# 1_PWR.net
KiCad netlist of a schematic drawn in Altium Designer
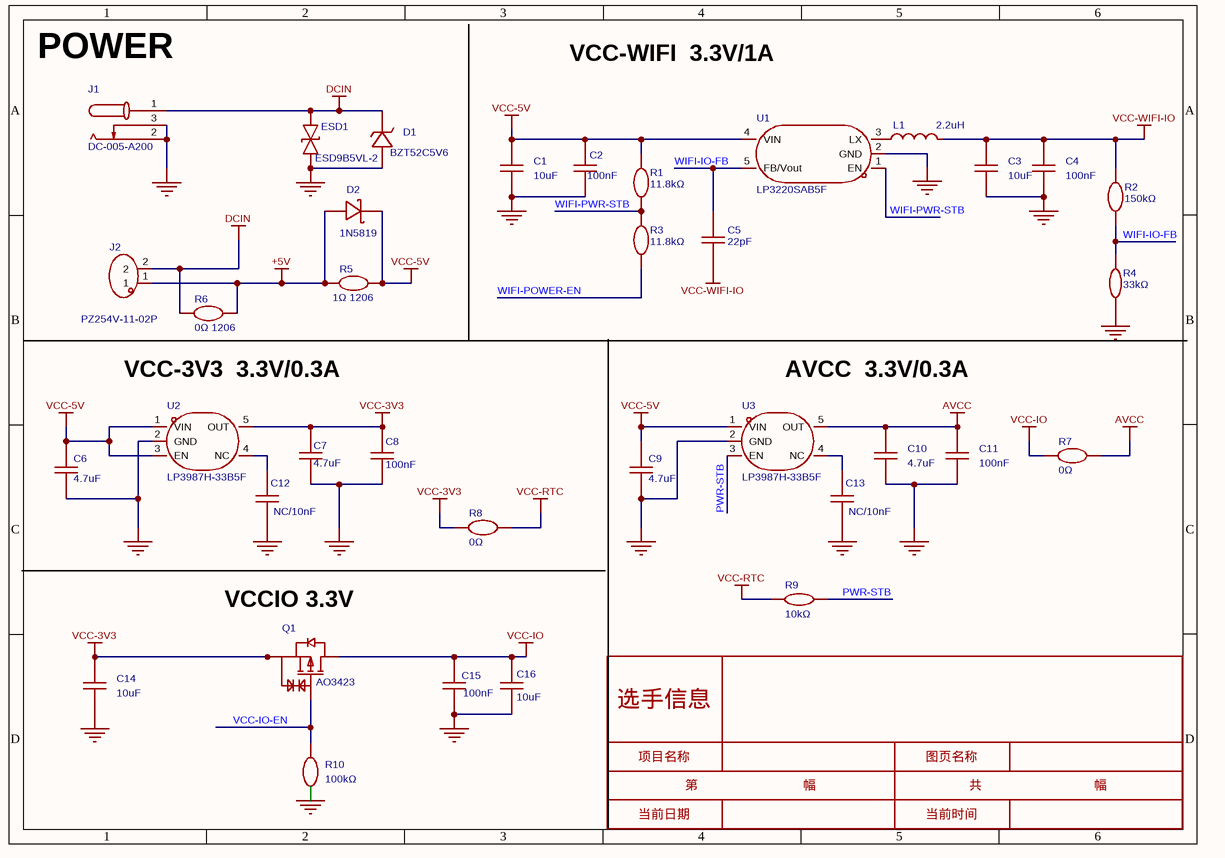
[diagram p0: 1_PWR.schdoc]

(export (version "E")
  (design (tool "Eeschema 10.0.6"))
  (components
    (comp (ref "C1")
      (value "10uF")
      (footprint "C0805")
      (description "容值:10uF;精度:±10%;额定电压:50V;温度系数:X5R;")
      (fields
        (field (name "MANUFACTURER") "HRE(芯声)")
        (field (name "MANUFACTURER PART") "CGA0805X5R106K500MT")
      )
      (libsource (lib "altium-import") (part "root_1_CGA0805X5R106K500MT_"))
    )
    (comp (ref "C2")
      (value "100nF")
      (footprint "C0402")
      (description "容值:100nF;精度:±10%;额定电压:16V;温度系数:X7R;")
      (fields
        (field (name "MANUFACTURER") "SAMSUNG(三星)")
        (field (name "MANUFACTURER PART") "CL05B104KO5NNNC")
      )
      (libsource (lib "altium-import") (part "root_1_CL05B104KO5NNNC_"))
    )
    (comp (ref "C3")
      (value "10uF")
      (footprint "C0805")
      (description "容值:10uF;精度:±10%;额定电压:50V;温度系数:X5R;")
      (fields
        (field (name "MANUFACTURER") "HRE(芯声)")
        (field (name "MANUFACTURER PART") "CGA0805X5R106K500MT")
      )
      (libsource (lib "altium-import") (part "root_1_CGA0805X5R106K500MT_"))
    )
    (comp (ref "C4")
      (value "100nF")
      (footprint "C0402")
      (description "容值:100nF;精度:±10%;额定电压:16V;温度系数:X7R;")
      (fields
        (field (name "MANUFACTURER") "SAMSUNG(三星)")
        (field (name "MANUFACTURER PART") "CL05B104KO5NNNC")
      )
      (libsource (lib "altium-import") (part "root_1_CL05B104KO5NNNC_"))
    )
    (comp (ref "C5")
      (value "22pF")
      (footprint "C0402")
      (description "容值:22pF;精度:±5%;额定电压:50V;温度系数:C0G;")
      (fields
        (field (name "MANUFACTURER") "FOJAN(富捷)")
        (field (name "MANUFACTURER PART") "FCC0402N220J500AT")
      )
      (libsource (lib "altium-import") (part "root_1_FCC0402N220J500AT_"))
    )
    (comp (ref "C6")
      (value "4.7uF")
      (footprint "C0402")
      (description "容值:4.7uF;精度:±20%;额定电压:25V;温度系数:-;")
      (fields
        (field (name "MANUFACTURER") "muRata(村田)")
        (field (name "MANUFACTURERPART") "GRM155C61E475ME15D")
      )
      (libsource (lib "altium-import") (part "root_1_GRM155C61E475ME15D_"))
    )
    (comp (ref "C7")
      (value "4.7uF")
      (footprint "C0402")
      (description "容值:4.7uF;精度:±20%;额定电压:25V;温度系数:-;")
      (fields
        (field (name "MANUFACTURER") "muRata(村田)")
        (field (name "MANUFACTURERPART") "GRM155C61E475ME15D")
      )
      (libsource (lib "altium-import") (part "root_1_GRM155C61E475ME15D_"))
    )
    (comp (ref "C8")
      (value "100nF")
      (footprint "C0402")
      (description "容值:100nF;精度:±10%;额定电压:16V;温度系数:X7R;")
      (fields (field (name "MANUFACTURER") "SAMSUNG(三星)") (field (name "MANUFACTURERPART") "CL05B104KO5NNNC"))
      (libsource (lib "altium-import") (part "root_1_CL05B104KO5NNNC_"))
    )
    (comp (ref "C9")
      (value "4.7uF")
      (footprint "C0402")
      (description "容值:4.7uF;精度:±20%;额定电压:25V;温度系数:-;")
      (fields
        (field (name "MANUFACTURER") "muRata(村田)")
        (field (name "MANUFACTURERPART") "GRM155C61E475ME15D")
      )
      (libsource (lib "altium-import") (part "root_1_GRM155C61E475ME15D_"))
    )
    (comp (ref "C10")
      (value "4.7uF")
      (footprint "C0402")
      (description "容值:4.7uF;精度:±20%;额定电压:25V;温度系数:-;")
      (fields
        (field (name "MANUFACTURER") "muRata(村田)")
        (field (name "MANUFACTURERPART") "GRM155C61E475ME15D")
      )
      (libsource (lib "altium-import") (part "root_1_GRM155C61E475ME15D_"))
    )
    (comp (ref "C11")
      (value "100nF")
      (footprint "C0402")
      (description "容值:100nF;精度:±10%;额定电压:16V;温度系数:X7R;")
      (fields (field (name "MANUFACTURER") "SAMSUNG(三星)") (field (name "MANUFACTURERPART") "CL05B104KO5NNNC"))
      (libsource (lib "altium-import") (part "root_1_CL05B104KO5NNNC_"))
    )
    (comp (ref "C12")
      (value "NC/10nF")
      (footprint "C0402")
      (description "容值:100nF;精度:±10%;额定电压:16V;温度系数:X7R;")
      (fields (field (name "MANUFACTURER") "SAMSUNG(三星)") (field (name "MANUFACTURERPART") "CL05B104KO5NNNC"))
      (libsource (lib "altium-import") (part "root_1_CL05B104KO5NNNC_"))
    )
    (comp (ref "C13")
      (value "NC/10nF")
      (footprint "C0402")
      (description "容值:100nF;精度:±10%;额定电压:16V;温度系数:X7R;")
      (fields (field (name "MANUFACTURER") "SAMSUNG(三星)") (field (name "MANUFACTURERPART") "CL05B104KO5NNNC"))
      (libsource (lib "altium-import") (part "root_1_CL05B104KO5NNNC_"))
    )
    (comp (ref "C14")
      (value "10uF")
      (footprint "C0805")
      (description "容值:10uF;精度:±10%;额定电压:50V;温度系数:X5R;")
      (fields (field (name "MANUFACTURER") "HRE(芯声)") (field (name "MANUFACTURERPART") "CGA0805X5R106K500MT"))
      (libsource (lib "altium-import") (part "root_1_mirrored_CGA0805X5R106K500MT_"))
    )
    (comp (ref "C15")
      (value "100nF")
      (footprint "C0402")
      (description "容值:100nF;精度:±10%;额定电压:16V;温度系数:X7R;")
      (fields (field (name "MANUFACTURER") "SAMSUNG(三星)") (field (name "MANUFACTURERPART") "CL05B104KO5NNNC"))
      (libsource (lib "altium-import") (part "root_1_mirrored_CL05B104KO5NNNC_"))
    )
    (comp (ref "C16")
      (value "10uF")
      (footprint "C0805")
      (description "容值:10uF;精度:±10%;额定电压:50V;温度系数:X5R;")
      (fields (field (name "MANUFACTURER") "HRE(芯声)") (field (name "MANUFACTURERPART") "CGA0805X5R106K500MT"))
      (libsource (lib "altium-import") (part "root_1_mirrored_CGA0805X5R106K500MT_"))
    )
    (comp (ref "D1")
      (value "BZT52C5V6")
      (footprint "SOD-123_L2.7-W1.6-LS3.7-RD")
      (description "二极管配置:独立式;稳压值(标称值):5.6V;稳压值(范围):5.32V~5.88V;耗散功率(Pd):350mW;")
      (fields (field (name "MANUFACTURER") "R+O(宏嘉诚)"))
      (libsource (lib "altium-import") (part "root_3_BZT52C5V6_C19077402_"))
    )
    (comp (ref "D2")
      (value "1N5819")
      (footprint "SMA_L4.4-W2.6-LS5.0-RD")
      (description "正向压降(Vf):500mV@1A;直流反向耐压(Vr):40V;整流电流:1A;")
      (fields (field (name "MANUFACTURER") "KEXIN(科信)"))
      (libsource (lib "altium-import") (part "root_2_1N5819_C437199_"))
    )
    (comp (ref "ESD1")
      (value "ESD9B5VL-2")
      (footprint "DFN1006-2L-BI")
      (description "反向截止电压(Vrwm):5V;钳位电压:12.5V;峰值脉冲功率(Ppp):80W@8/20us;击穿电压:6V;")
      (fields (field (name "MANUFACTURER") "Leiditech(雷卯电子)"))
      (libsource (lib "altium-import") (part "root_1_ESD9B5VL-2_"))
    )
    (comp (ref "J1")
      (value "DC-005-A200")
      (footprint "DC-IN-TH_DC-005-A200")
      (description "连接器类型:DC电源插座;安装方式:弯插;触点内径:2mm;触点外径:6.4mm;额定电流:3A;额定电压:30V;工作温度:-20℃~+70℃;")
      (fields (field (name "MANUFACTURER") "XUNPU(讯普)"))
      (libsource (lib "altium-import") (part "root_0_DC-005-A200_"))
    )
    (comp (ref "J2")
      (value "PZ254V-11-02P")
      (footprint "HDR-TH_2P-P2.54-V-M")
      (fields (field (name "MANUFACTURER") "XFCN(兴飞)"))
      (libsource (lib "altium-import") (part "root_2_PZ254V-11-02P_"))
    )
    (comp (ref "L1")
      (value "2.2uH")
      (footprint "IND-SMD_L4.6-W4.1_MHCI04015")
      (description "电感值:2.2uH;精度:±20%;额定电流:4A;饱和电流(Isat):5A;类型:一体成型电感;")
      (fields (field (name "MANUFACTURER") "JIERR(捷而瑞)") (field (name "MANUFACTURER PART") "SRG0420-2R2-M"))
      (libsource (lib "altium-import") (part "root_0_SRG0420-2R2-M_"))
    )
    (comp (ref "Q1")
      (value "AO3423")
      (footprint "SOT-23-3_L2.9-W1.3-P1.90-LS2.4-BR-3")
      (fields (field (name "MANUFACTURER") "TECH PUBLIC(台舟)"))
      (libsource (lib "altium-import") (part "root_1_mirrored_AO3423_C19268144_"))
    )
    (comp (ref "R1")
      (value "11.8kΩ")
      (footprint "R0402")
      (description "电阻类型:厚膜电阻;阻值:11.8kΩ;精度:±1%;功率:62.5mW;工作电压:50V;温度系数:±100ppm/℃;")
      (fields (field (name "MANUFACTURER") "FOJAN(富捷)") (field (name "MANUFACTURER PART") "FRC0402F1182TS"))
      (libsource (lib "altium-import") (part "root_1_FRC0402F1182TS_"))
    )
    (comp (ref "R2")
      (value "150kΩ")
      (footprint "R0402")
      (description "电阻类型:厚膜电阻;阻值:150kΩ;精度:±1%;功率:62.5mW;工作电压:50V;温度系数:±100ppm/℃;")
      (fields (field (name "MANUFACTURER") "FOJAN(富捷)") (field (name "MANUFACTURER PART") "FRC0402F1503TS"))
      (libsource (lib "altium-import") (part "root_1_FRC0402F1503TS_"))
    )
    (comp (ref "R3")
      (value "11.8kΩ")
      (footprint "R0402")
      (description "电阻类型:厚膜电阻;阻值:11.8kΩ;精度:±1%;功率:62.5mW;工作电压:50V;温度系数:±100ppm/℃;")
      (fields (field (name "MANUFACTURER") "FOJAN(富捷)") (field (name "MANUFACTURER PART") "FRC0402F1182TS"))
      (libsource (lib "altium-import") (part "root_1_FRC0402F1182TS_"))
    )
    (comp (ref "R4")
      (value "33kΩ")
      (footprint "R0402")
      (description "电阻类型:厚膜电阻;阻值:33kΩ;精度:±1%;功率:62.5mW;最大工作电压:50V;温度系数:±100ppm/℃;")
      (fields
        (field (name "MANUFACTURER") "UNI-ROYAL(厚声)")
        (field (name "MANUFACTURER PART") "0402WGF3302TCE")
      )
      (libsource (lib "altium-import") (part "root_1_0402WGF3302TCE_"))
    )
    (comp (ref "R5")
      (value "1Ω 1206")
      (footprint "R1206")
      (description "电阻类型:厚膜电阻;阻值:1Ω;精度:±5%;功率:250mW;工作电压:200V;温度系数:±200ppm/℃;")
      (fields (field (name "MANUFACTURER") "FOJAN(富捷)") (field (name "MANUFACTURERPART") "FRC1206J1R0 TS"))
      (libsource (lib "altium-import") (part "root_0_FRC1206J1R0 TS_"))
    )
    (comp (ref "R6")
      (value "0Ω 1206")
      (footprint "R1206")
      (description "电阻类型:厚膜电阻;阻值:0Ω;精度:±5%;功率:250mW;工作电压:200V;")
      (fields (field (name "MANUFACTURER") "FOJAN(富捷)") (field (name "MANUFACTURERPART") "FRC1206P000 TS"))
      (libsource (lib "altium-import") (part "root_0_FRC1206P000 TS_"))
    )
    (comp (ref "R7")
      (value "0Ω")
      (footprint "R0402")
      (description "电阻类型:厚膜电阻;阻值:0Ω;精度:±5%;功率:62.5mW;工作电压:50V;")
      (fields (field (name "MANUFACTURER") "FOJAN(富捷)") (field (name "MANUFACTURERPART") "FRC0402P000 TS"))
      (libsource (lib "altium-import") (part "root_0_FRC0402P000 TS_"))
    )
    (comp (ref "R8")
      (value "0Ω")
      (footprint "R0402")
      (description "电阻类型:厚膜电阻;阻值:0Ω;精度:±5%;功率:62.5mW;工作电压:50V;")
      (fields (field (name "MANUFACTURER") "FOJAN(富捷)") (field (name "MANUFACTURERPART") "FRC0402P000 TS"))
      (libsource (lib "altium-import") (part "root_0_FRC0402P000 TS_"))
    )
    (comp (ref "R9")
      (value "10kΩ")
      (footprint "R0402")
      (description "电阻类型:厚膜电阻;阻值:10kΩ;精度:±1%;功率:62.5mW;工作电压:50V;温度系数:±100ppm/℃;")
      (fields (field (name "MANUFACTURER") "YAGEO(国巨)") (field (name "MANUFACTURERPART") "RC0402FR-0710KL"))
      (libsource (lib "altium-import") (part "root_0_RC0402FR-0710KL_"))
    )
    (comp (ref "R10")
      (value "100kΩ")
      (footprint "R0402")
      (description "电阻类型:薄膜电阻;阻值:100kΩ;精度:±0.1%;功率:62.5mW;最大工作电压:50V;温度系数:±25ppm/℃;")
      (fields (field (name "MANUFACTURER") "YAGEO(国巨)") (field (name "MANUFACTURERPART") "RT0402BRD07100KL"))
      (libsource (lib "altium-import") (part "root_3_RT0402BRD07100KL_"))
    )
    (comp (ref "U1")
      (value "LP3220SAB5F")
      (footprint "SOT-23-5_L3.0-W1.7-P0.95-LS2.8-BR")
      (description "功能类型:降压型;工作电压:2.2V~5.5V;输出电压:610mV~5.5V;输出电流:1A;输出类型:可调;")
      (fields (field (name "MANUFACTURER") "LOWPOWER(微源半导体)"))
      (libsource (lib "altium-import") (part "root_2_LP3220SAB5F_"))
    )
    (comp (ref "U2")
      (value "LP3987H-33B5F")
      (footprint "SOT-23-5_L3.0-W1.7-P0.95-LS2.8-BL")
      (description "输出类型:固定;工作电压:6V;输出电压:3.3V;输出电流:600mA;电源纹波抑制比(PSRR):65dB@(1kHz);输出极性:正极;")
      (fields (field (name "MANUFACTURER") "LOWPOWER(微源半导体)"))
      (libsource (lib "altium-import") (part "root_0_LP3987H-33B5F_"))
    )
    (comp (ref "U3")
      (value "LP3987H-33B5F")
      (footprint "SOT-23-5_L3.0-W1.7-P0.95-LS2.8-BL")
      (description "输出类型:固定;工作电压:6V;输出电压:3.3V;输出电流:600mA;电源纹波抑制比(PSRR):65dB@(1kHz);输出极性:正极;")
      (fields (field (name "MANUFACTURER") "LOWPOWER(微源半导体)"))
      (libsource (lib "altium-import") (part "root_0_LP3987H-33B5F_"))
    )
  )
  (nets
    (net (code "1") (name "+5V") (class "Default")
      (node (ref "D2") (pin "2") (pinfunction "A_2") (pintype "passive"))
      (node (ref "J2") (pin "1") (pinfunction "1_1") (pintype "passive"))
      (node (ref "R5") (pin "1") (pinfunction "1_1") (pintype "passive"))
      (node (ref "R6") (pin "2") (pinfunction "2_2") (pintype "passive"))
    )
    (net (code "2") (name "/PWR-STB") (class "Default")
      (node (ref "R9") (pin "2") (pinfunction "2_2") (pintype "passive"))
      (node (ref "U3") (pin "3") (pinfunction "EN_3") (pintype "passive"))
    )
    (net (code "3") (name "/VCC-IO-EN") (class "Default")
      (node (ref "Q1") (pin "1") (pinfunction "G_1") (pintype "passive"))
      (node (ref "R10") (pin "1") (pinfunction "1_1") (pintype "passive"))
    )
    (net (code "4") (name "/WIFI-IO-FB") (class "Default")
      (node (ref "C5") (pin "2") (pinfunction "2_2") (pintype "passive"))
      (node (ref "R2") (pin "1") (pinfunction "1_1") (pintype "passive"))
      (node (ref "R4") (pin "2") (pinfunction "2_2") (pintype "passive"))
      (node (ref "U1") (pin "5") (pinfunction "FB/Vout_5") (pintype "passive"))
    )
    (net (code "5") (name "/WIFI-POWER-EN") (class "Default")
      (node (ref "R3") (pin "1") (pinfunction "1_1") (pintype "passive"))
    )
    (net (code "6") (name "/WIFI-PWR-STB") (class "Default")
      (node (ref "R1") (pin "1") (pinfunction "1_1") (pintype "passive"))
      (node (ref "R3") (pin "2") (pinfunction "2_2") (pintype "passive"))
      (node (ref "U1") (pin "1") (pinfunction "EN_1") (pintype "passive"))
    )
    (net (code "7") (name "AVCC") (class "Default")
      (node (ref "C10") (pin "2") (pinfunction "2_2") (pintype "passive"))
      (node (ref "C11") (pin "2") (pinfunction "2_2") (pintype "passive"))
      (node (ref "R7") (pin "2") (pinfunction "2_2") (pintype "passive"))
      (node (ref "U3") (pin "5") (pinfunction "OUT_5") (pintype "passive"))
    )
    (net (code "8") (name "DCIN") (class "Default")
      (node (ref "D1") (pin "1") (pinfunction "K_1") (pintype "passive"))
      (node (ref "ESD1") (pin "2") (pinfunction "2_2") (pintype "passive"))
      (node (ref "J1") (pin "1") (pinfunction "1_1") (pintype "passive"))
      (node (ref "J2") (pin "2") (pinfunction "2_2") (pintype "passive"))
      (node (ref "R6") (pin "1") (pinfunction "1_1") (pintype "passive"))
    )
    (net (code "9") (name "GND") (class "Default")
      (node (ref "C1") (pin "1") (pinfunction "1_1") (pintype "passive"))
      (node (ref "C10") (pin "1") (pinfunction "1_1") (pintype "passive"))
      (node (ref "C11") (pin "1") (pinfunction "1_1") (pintype "passive"))
      (node (ref "C12") (pin "1") (pinfunction "1_1") (pintype "passive"))
      (node (ref "C13") (pin "1") (pinfunction "1_1") (pintype "passive"))
      (node (ref "C14") (pin "1") (pinfunction "1_1") (pintype "passive"))
      (node (ref "C15") (pin "1") (pinfunction "1_1") (pintype "passive"))
      (node (ref "C16") (pin "1") (pinfunction "1_1") (pintype "passive"))
      (node (ref "C2") (pin "1") (pinfunction "1_1") (pintype "passive"))
      (node (ref "C3") (pin "1") (pinfunction "1_1") (pintype "passive"))
      (node (ref "C4") (pin "1") (pinfunction "1_1") (pintype "passive"))
      (node (ref "C6") (pin "1") (pinfunction "1_1") (pintype "passive"))
      (node (ref "C7") (pin "1") (pinfunction "1_1") (pintype "passive"))
      (node (ref "C8") (pin "1") (pinfunction "1_1") (pintype "passive"))
      (node (ref "C9") (pin "1") (pinfunction "1_1") (pintype "passive"))
      (node (ref "D1") (pin "2") (pinfunction "A_2") (pintype "passive"))
      (node (ref "ESD1") (pin "1") (pinfunction "1_1") (pintype "passive"))
      (node (ref "J1") (pin "2") (pinfunction "2_2") (pintype "passive"))
      (node (ref "J1") (pin "3") (pinfunction "3_3") (pintype "passive"))
      (node (ref "R10") (pin "2") (pinfunction "2_2") (pintype "passive"))
      (node (ref "R4") (pin "1") (pinfunction "1_1") (pintype "passive"))
      (node (ref "U1") (pin "2") (pinfunction "GND_2") (pintype "passive"))
      (node (ref "U2") (pin "2") (pinfunction "GND_2") (pintype "passive"))
      (node (ref "U3") (pin "2") (pinfunction "GND_2") (pintype "passive"))
    )
    (net (code "10") (name "Net-(U1-LX)") (class "Default")
      (node (ref "L1") (pin "1") (pinfunction "1_1") (pintype "passive"))
      (node (ref "U1") (pin "3") (pinfunction "LX_3") (pintype "passive"))
    )
    (net (code "11") (name "Net-(U2-NC)") (class "Default")
      (node (ref "C12") (pin "2") (pinfunction "2_2") (pintype "passive"))
      (node (ref "U2") (pin "4") (pinfunction "NC_4") (pintype "passive"))
    )
    (net (code "12") (name "Net-(U3-NC)") (class "Default")
      (node (ref "C13") (pin "2") (pinfunction "2_2") (pintype "passive"))
      (node (ref "U3") (pin "4") (pinfunction "NC_4") (pintype "passive"))
    )
    (net (code "13") (name "VCC-3V3") (class "Default")
      (node (ref "C14") (pin "2") (pinfunction "2_2") (pintype "passive"))
      (node (ref "C7") (pin "2") (pinfunction "2_2") (pintype "passive"))
      (node (ref "C8") (pin "2") (pinfunction "2_2") (pintype "passive"))
      (node (ref "Q1") (pin "2") (pinfunction "S_2") (pintype "passive"))
      (node (ref "R8") (pin "1") (pinfunction "1_1") (pintype "passive"))
      (node (ref "U2") (pin "5") (pinfunction "OUT_5") (pintype "passive"))
    )
    (net (code "14") (name "VCC-5V") (class "Default")
      (node (ref "C1") (pin "2") (pinfunction "2_2") (pintype "passive"))
      (node (ref "C2") (pin "2") (pinfunction "2_2") (pintype "passive"))
      (node (ref "C6") (pin "2") (pinfunction "2_2") (pintype "passive"))
      (node (ref "C9") (pin "2") (pinfunction "2_2") (pintype "passive"))
      (node (ref "D2") (pin "1") (pinfunction "C_1") (pintype "passive"))
      (node (ref "R1") (pin "2") (pinfunction "2_2") (pintype "passive"))
      (node (ref "R5") (pin "2") (pinfunction "2_2") (pintype "passive"))
      (node (ref "U1") (pin "4") (pinfunction "VIN_4") (pintype "passive"))
      (node (ref "U2") (pin "1") (pinfunction "VIN_1") (pintype "passive"))
      (node (ref "U2") (pin "3") (pinfunction "EN_3") (pintype "passive"))
      (node (ref "U3") (pin "1") (pinfunction "VIN_1") (pintype "passive"))
    )
    (net (code "15") (name "VCC-IO") (class "Default")
      (node (ref "C15") (pin "2") (pinfunction "2_2") (pintype "passive"))
      (node (ref "C16") (pin "2") (pinfunction "2_2") (pintype "passive"))
      (node (ref "Q1") (pin "3") (pinfunction "D_3") (pintype "passive"))
      (node (ref "R7") (pin "1") (pinfunction "1_1") (pintype "passive"))
    )
    (net (code "16") (name "VCC-RTC") (class "Default")
      (node (ref "R8") (pin "2") (pinfunction "2_2") (pintype "passive"))
      (node (ref "R9") (pin "1") (pinfunction "1_1") (pintype "passive"))
    )
    (net (code "17") (name "VCC-WIFI-IO") (class "Default")
      (node (ref "C3") (pin "2") (pinfunction "2_2") (pintype "passive"))
      (node (ref "C4") (pin "2") (pinfunction "2_2") (pintype "passive"))
      (node (ref "C5") (pin "1") (pinfunction "1_1") (pintype "passive"))
      (node (ref "L1") (pin "2") (pinfunction "2_2") (pintype "passive"))
      (node (ref "R2") (pin "2") (pinfunction "2_2") (pintype "passive"))
    )
  )
)
